# painel_meb.net
KiCad netlist of a schematic drawn in Altium Designer
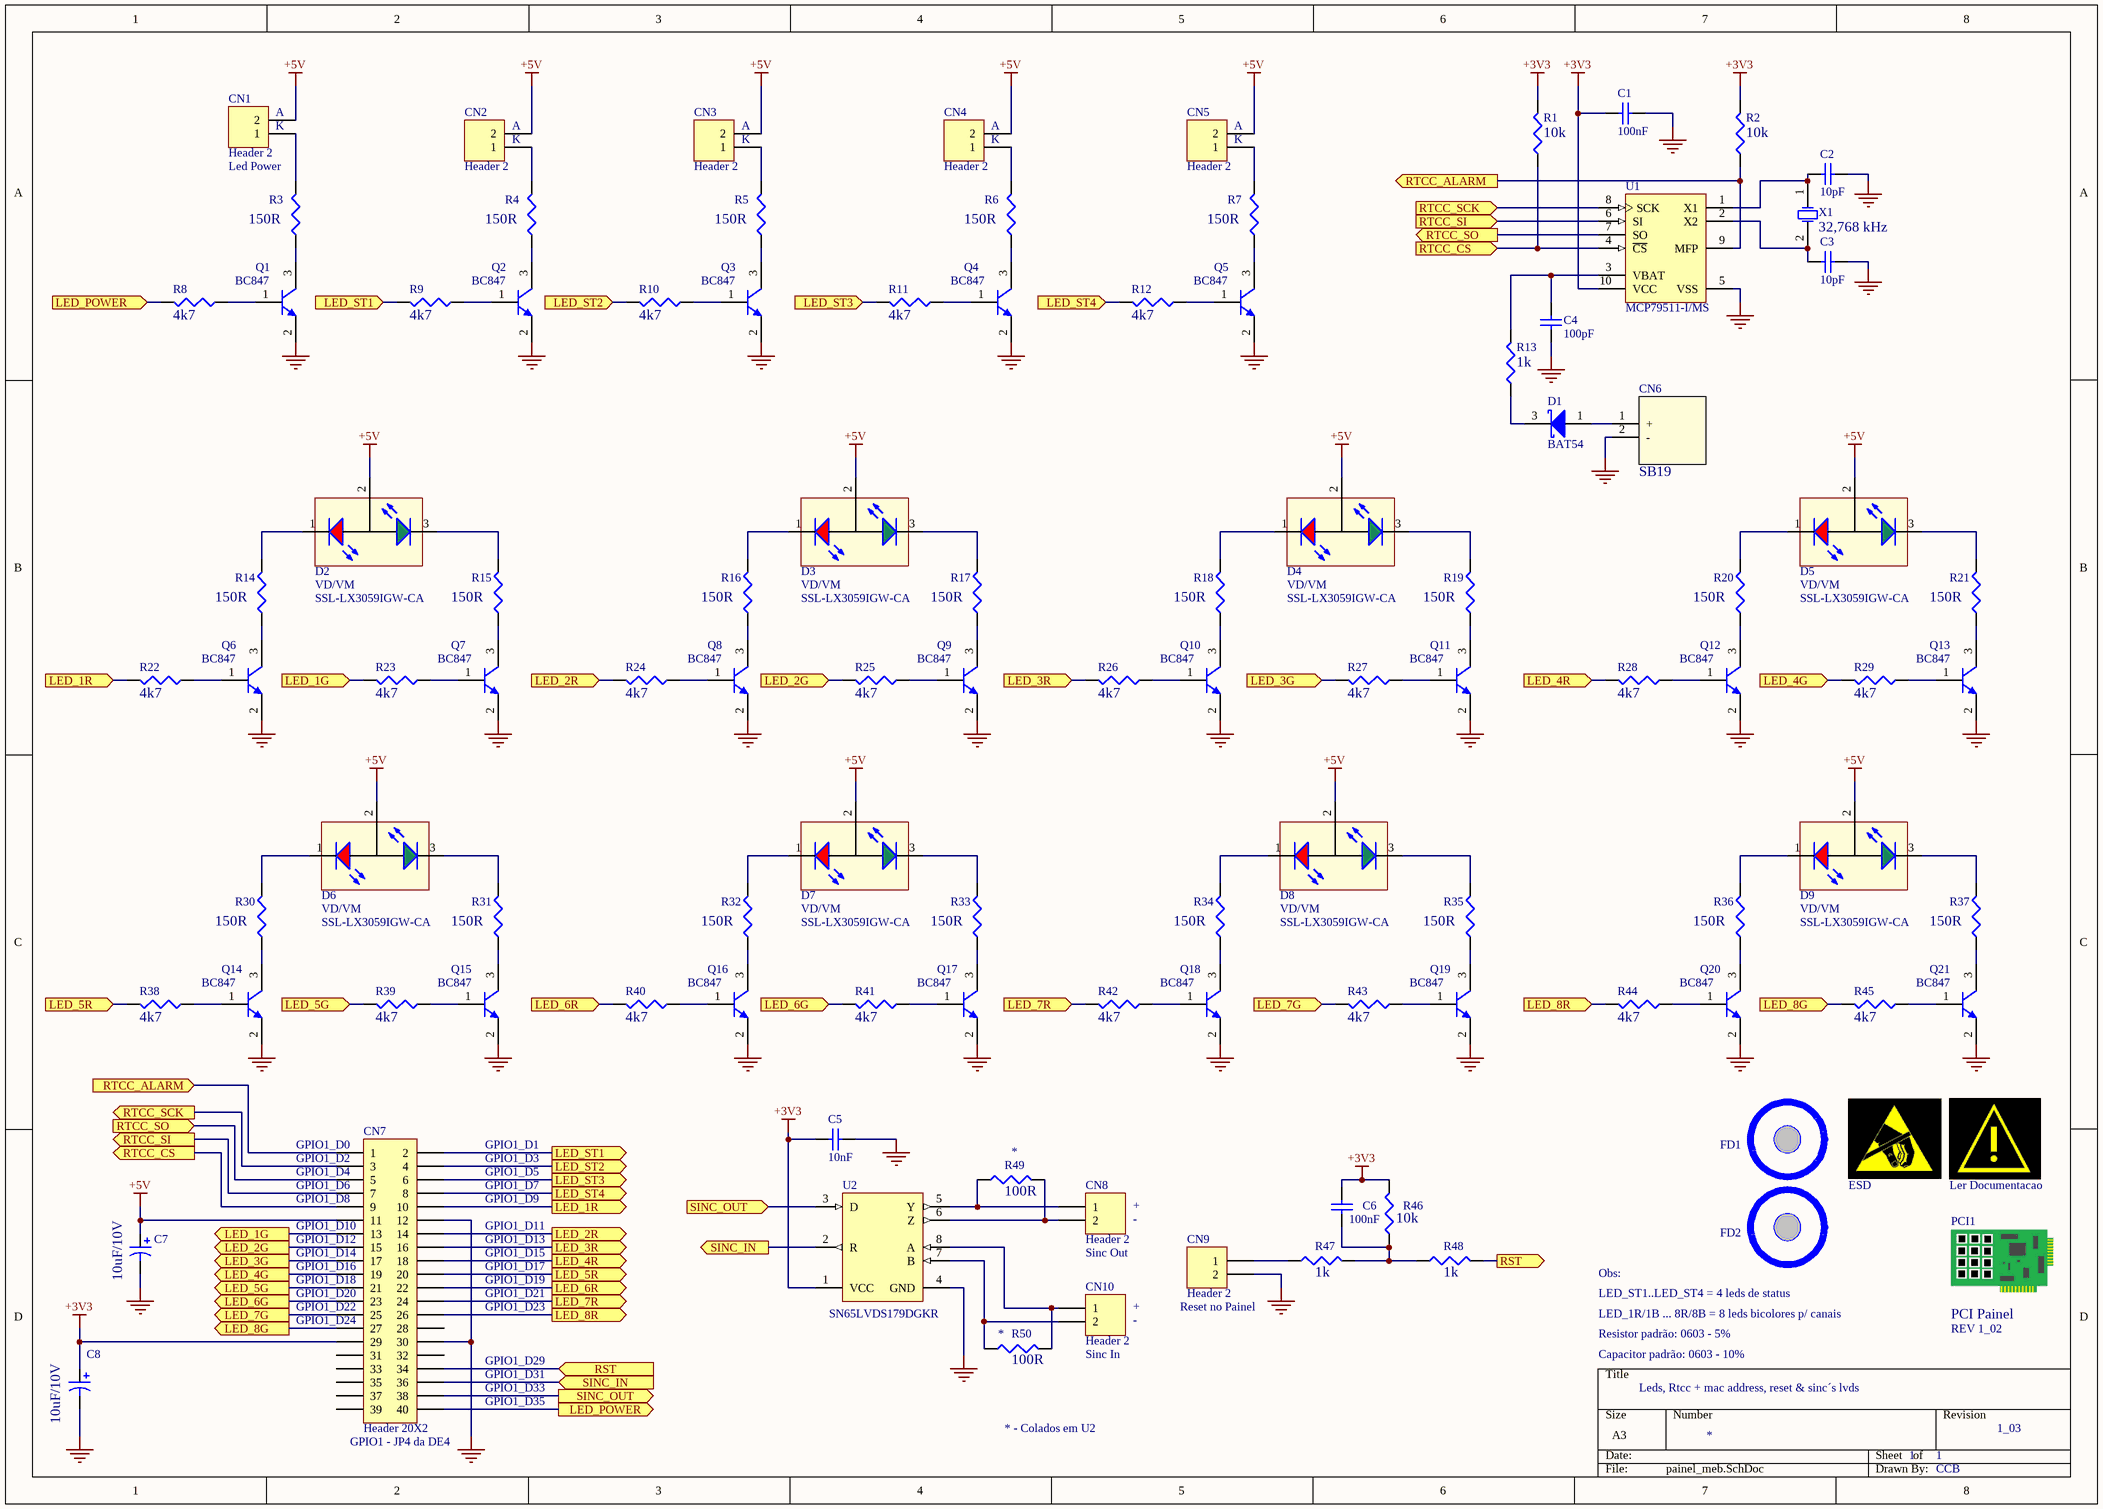
[diagram p0: painel_meb.SchDoc]

(export (version "E")
  (design (tool "Eeschema 10.0.6"))
  (components
    (comp (ref "AT1")
      (value "##nl")
      (footprint "LEIA_DOCUMENTACAO")
      (description "ATENCAO")
      (fields (field (name "VALOR") "Ler Documentacao"))
      (libsource (lib "SIMBOLOS") (part "ATENCAO"))
    )
    (comp (ref "C1")
      (value "Capacitor Cerâmico SMD")
      (footprint "0603 - CAP - montagem na maquina")
      (fields (field (name "VALOR") "100nF"))
      (libsource (lib "Miscellaneous Devices") (part "Capacitor Cerâmico SMD"))
    )
    (comp (ref "C2")
      (value "Capacitor Cerâmico SMD")
      (footprint "0603 - CAP - montagem na maquina")
      (fields (field (name "VALOR") "10pF"))
      (libsource (lib "Miscellaneous Devices") (part "Capacitor Cerâmico SMD"))
    )
    (comp (ref "C3")
      (value "Capacitor Cerâmico SMD")
      (footprint "0603 - CAP - montagem na maquina")
      (fields (field (name "VALOR") "10pF"))
      (libsource (lib "Miscellaneous Devices") (part "Capacitor Cerâmico SMD"))
    )
    (comp (ref "C4")
      (value "Capacitor Cerâmico SMD")
      (footprint "0603 - CAP - montagem na maquina")
      (fields (field (name "VALOR") "100pF"))
      (libsource (lib "Miscellaneous Devices") (part "Capacitor Cerâmico SMD"))
    )
    (comp (ref "C5")
      (value "Capacitor Cerâmico SMD")
      (footprint "0603 - CAP - montagem na maquina")
      (fields (field (name "VALOR") "10nF"))
      (libsource (lib "Miscellaneous Devices") (part "Capacitor Cerâmico SMD"))
    )
    (comp (ref "C6")
      (value "Capacitor Cerâmico SMD")
      (footprint "0603 - CAP - montagem na maquina")
      (fields (field (name "VALOR") "100nF"))
      (libsource (lib "Miscellaneous Devices") (part "Capacitor Cerâmico SMD"))
    )
    (comp (ref "C7")
      (value "Capacitor de tântalo")
      (footprint "CASE-B")
      (fields (field (name "VALOR") "10uF/10V"))
      (libsource (lib "Miscellaneous Devices") (part "Capacitor de tântalo"))
    )
    (comp (ref "C8")
      (value "Capacitor de tântalo")
      (footprint "CASE-B")
      (fields (field (name "VALOR") "10uF/10V"))
      (libsource (lib "Miscellaneous Devices") (part "Capacitor de tântalo"))
    )
    (comp (ref "CN1")
      (value "Header 2")
      (footprint "HDR1X2")
      (description "Header, 2-Pin")
      (fields (field (name "PUBLISHER") "Altium Limited"))
      (libsource (lib "Miscellaneous Connectors") (part "Header 2"))
    )
    (comp (ref "CN2")
      (value "Header 2")
      (footprint "HDR1X2")
      (description "Header, 2-Pin")
      (fields (field (name "PUBLISHER") "Altium Limited"))
      (libsource (lib "Miscellaneous Connectors") (part "Header 2"))
    )
    (comp (ref "CN3")
      (value "Header 2")
      (footprint "HDR1X2")
      (description "Header, 2-Pin")
      (fields (field (name "PUBLISHER") "Altium Limited"))
      (libsource (lib "Miscellaneous Connectors") (part "Header 2"))
    )
    (comp (ref "CN4")
      (value "Header 2")
      (footprint "HDR1X2")
      (description "Header, 2-Pin")
      (fields (field (name "PUBLISHER") "Altium Limited"))
      (libsource (lib "Miscellaneous Connectors") (part "Header 2"))
    )
    (comp (ref "CN5")
      (value "Header 2")
      (footprint "HDR1X2")
      (description "Header, 2-Pin")
      (fields (field (name "PUBLISHER") "Altium Limited"))
      (libsource (lib "Miscellaneous Connectors") (part "Header 2"))
    )
    (comp (ref "CN6")
      (value "11.0137")
      (footprint "Soquete para bateria SB19")
      (description "Soquete para Bateria CR2032")
      (fields (field (name "PART NUMBER") "SB19"))
      (libsource (lib "METALTEX") (part "Soquete para Bateria CR2032"))
    )
    (comp (ref "CN7")
      (value "Header 20X2")
      (footprint "HDR2X20")
      (description "Header, 20-Pin, Dual row")
      (fields (field (name "PUBLISHER") "Altium Limited"))
      (libsource (lib "Miscellaneous Connectors") (part "Header 20X2"))
    )
    (comp (ref "CN8")
      (value "Header 2")
      (footprint "HDR1X2")
      (description "Header, 2-Pin")
      (fields (field (name "PUBLISHER") "Altium Limited"))
      (libsource (lib "") (part "Header 2_1"))
    )
    (comp (ref "CN9")
      (value "Header 2")
      (footprint "HDR1X2")
      (description "Header, 2-Pin")
      (fields (field (name "PUBLISHER") "Altium Limited"))
      (libsource (lib "") (part "Header 2_2"))
    )
    (comp (ref "CN10")
      (value "Header 2")
      (footprint "HDR1X2")
      (description "Header, 2-Pin")
      (fields (field (name "PUBLISHER") "Altium Limited"))
      (libsource (lib "") (part "Header 2_1"))
    )
    (comp (ref "D1")
      (value "04.0100")
      (footprint "SOT23-3N - BAT54FAIRCHILD")
      (description "Diodo Schottky")
      (fields (field (name "PART NUMBER") "BAT54"))
      (libsource (lib "FSC Discrete Diode") (part "BAT54"))
    )
    (comp (ref "D2")
      (value "SSL-LX3059IGW-CA")
      (footprint "Led 3mm bicolor")
      (description "Led bicolor pth 3mm verde/vermelho")
      (fields (field (name "VALOR") "VD/VM") (field (name "PART NUMBER") "SSL-LX3059IGW-CA"))
      (libsource (lib "lumex") (part "SSL-LX3059IGW-CA"))
    )
    (comp (ref "D3")
      (value "SSL-LX3059IGW-CA")
      (footprint "Led 3mm bicolor")
      (description "Led bicolor pth 3mm verde/vermelho")
      (fields (field (name "VALOR") "VD/VM") (field (name "PART NUMBER") "SSL-LX3059IGW-CA"))
      (libsource (lib "lumex") (part "SSL-LX3059IGW-CA"))
    )
    (comp (ref "D4")
      (value "SSL-LX3059IGW-CA")
      (footprint "Led 3mm bicolor")
      (description "Led bicolor pth 3mm verde/vermelho")
      (fields (field (name "VALOR") "VD/VM") (field (name "PART NUMBER") "SSL-LX3059IGW-CA"))
      (libsource (lib "lumex") (part "SSL-LX3059IGW-CA"))
    )
    (comp (ref "D5")
      (value "SSL-LX3059IGW-CA")
      (footprint "Led 3mm bicolor")
      (description "Led bicolor pth 3mm verde/vermelho")
      (fields (field (name "VALOR") "VD/VM") (field (name "PART NUMBER") "SSL-LX3059IGW-CA"))
      (libsource (lib "lumex") (part "SSL-LX3059IGW-CA"))
    )
    (comp (ref "D6")
      (value "SSL-LX3059IGW-CA")
      (footprint "Led 3mm bicolor")
      (description "Led bicolor pth 3mm verde/vermelho")
      (fields (field (name "VALOR") "VD/VM") (field (name "PART NUMBER") "SSL-LX3059IGW-CA"))
      (libsource (lib "lumex") (part "SSL-LX3059IGW-CA"))
    )
    (comp (ref "D7")
      (value "SSL-LX3059IGW-CA")
      (footprint "Led 3mm bicolor")
      (description "Led bicolor pth 3mm verde/vermelho")
      (fields (field (name "VALOR") "VD/VM") (field (name "PART NUMBER") "SSL-LX3059IGW-CA"))
      (libsource (lib "lumex") (part "SSL-LX3059IGW-CA"))
    )
    (comp (ref "D8")
      (value "SSL-LX3059IGW-CA")
      (footprint "Led 3mm bicolor")
      (description "Led bicolor pth 3mm verde/vermelho")
      (fields (field (name "VALOR") "VD/VM") (field (name "PART NUMBER") "SSL-LX3059IGW-CA"))
      (libsource (lib "lumex") (part "SSL-LX3059IGW-CA"))
    )
    (comp (ref "D9")
      (value "SSL-LX3059IGW-CA")
      (footprint "Led 3mm bicolor")
      (description "Led bicolor pth 3mm verde/vermelho")
      (fields (field (name "VALOR") "VD/VM") (field (name "PART NUMBER") "SSL-LX3059IGW-CA"))
      (libsource (lib "lumex") (part "SSL-LX3059IGW-CA"))
    )
    (comp (ref "ESD1")
      (value "##nl")
      (footprint "ESTATICA")
      (description "ESD")
      (fields (field (name "VALOR") "ESD"))
      (libsource (lib "SIMBOLOS") (part "ESD"))
    )
    (comp (ref "FD1")
      (value "##nl")
      (footprint "FIDUCIAL")
      (description "Fiducial")
      (libsource (lib "PERIFERICOS") (part "Fiducial"))
    )
    (comp (ref "FD2")
      (value "##nl")
      (footprint "FIDUCIAL")
      (description "Fiducial")
      (libsource (lib "PERIFERICOS") (part "Fiducial"))
    )
    (comp (ref "PCI1")
      (value "30.????")
      (description "PCI")
      (fields (field (name "VALOR") "PCI Painel") (field (name "REV") "REV 1_02"))
      (libsource (lib "PCI") (part "PCI"))
    )
    (comp (ref "Q1")
      (value "QNPN")
      (footprint "SOT-23B")
      (description "NPN Bipolar Transistor")
      (fields (field (name "ALTIUM_UNNAMED_1") "BC847") (field (name "PUBLISHER") "Altium Limited"))
      (libsource (lib "Miscellaneous Devices") (part "QNPN"))
    )
    (comp (ref "Q2")
      (value "QNPN")
      (footprint "SOT-23B")
      (description "NPN Bipolar Transistor")
      (fields (field (name "VALOR") "BC847") (field (name "PUBLISHER") "Altium Limited"))
      (libsource (lib "Miscellaneous Devices") (part "QNPN"))
    )
    (comp (ref "Q3")
      (value "QNPN")
      (footprint "SOT-23B")
      (description "NPN Bipolar Transistor")
      (fields (field (name "ALTIUM_UNNAMED_1") "BC847") (field (name "PUBLISHER") "Altium Limited"))
      (libsource (lib "Miscellaneous Devices") (part "QNPN"))
    )
    (comp (ref "Q4")
      (value "QNPN")
      (footprint "SOT-23B")
      (description "NPN Bipolar Transistor")
      (fields (field (name "ALTIUM_UNNAMED_1") "BC847") (field (name "PUBLISHER") "Altium Limited"))
      (libsource (lib "Miscellaneous Devices") (part "QNPN"))
    )
    (comp (ref "Q5")
      (value "QNPN")
      (footprint "SOT-23B")
      (description "NPN Bipolar Transistor")
      (fields (field (name "ALTIUM_UNNAMED_1") "BC847") (field (name "PUBLISHER") "Altium Limited"))
      (libsource (lib "Miscellaneous Devices") (part "QNPN"))
    )
    (comp (ref "Q6")
      (value "QNPN")
      (footprint "SOT-23B")
      (description "NPN Bipolar Transistor")
      (fields (field (name "ALTIUM_UNNAMED_1") "BC847") (field (name "PUBLISHER") "Altium Limited"))
      (libsource (lib "Miscellaneous Devices") (part "QNPN"))
    )
    (comp (ref "Q7")
      (value "QNPN")
      (footprint "SOT-23B")
      (description "NPN Bipolar Transistor")
      (fields (field (name "ALTIUM_UNNAMED_1") "BC847") (field (name "PUBLISHER") "Altium Limited"))
      (libsource (lib "Miscellaneous Devices") (part "QNPN"))
    )
    (comp (ref "Q8")
      (value "QNPN")
      (footprint "SOT-23B")
      (description "NPN Bipolar Transistor")
      (fields (field (name "ALTIUM_UNNAMED_1") "BC847") (field (name "PUBLISHER") "Altium Limited"))
      (libsource (lib "Miscellaneous Devices") (part "QNPN"))
    )
    (comp (ref "Q9")
      (value "QNPN")
      (footprint "SOT-23B")
      (description "NPN Bipolar Transistor")
      (fields (field (name "ALTIUM_UNNAMED_1") "BC847") (field (name "PUBLISHER") "Altium Limited"))
      (libsource (lib "Miscellaneous Devices") (part "QNPN"))
    )
    (comp (ref "Q10")
      (value "QNPN")
      (footprint "SOT-23B")
      (description "NPN Bipolar Transistor")
      (fields (field (name "ALTIUM_UNNAMED_1") "BC847") (field (name "PUBLISHER") "Altium Limited"))
      (libsource (lib "Miscellaneous Devices") (part "QNPN"))
    )
    (comp (ref "Q11")
      (value "QNPN")
      (footprint "SOT-23B")
      (description "NPN Bipolar Transistor")
      (fields (field (name "ALTIUM_UNNAMED_1") "BC847") (field (name "PUBLISHER") "Altium Limited"))
      (libsource (lib "Miscellaneous Devices") (part "QNPN"))
    )
    (comp (ref "Q12")
      (value "QNPN")
      (footprint "SOT-23B")
      (description "NPN Bipolar Transistor")
      (fields (field (name "ALTIUM_UNNAMED_1") "BC847") (field (name "PUBLISHER") "Altium Limited"))
      (libsource (lib "Miscellaneous Devices") (part "QNPN"))
    )
    (comp (ref "Q13")
      (value "QNPN")
      (footprint "SOT-23B")
      (description "NPN Bipolar Transistor")
      (fields (field (name "ALTIUM_UNNAMED_1") "BC847") (field (name "PUBLISHER") "Altium Limited"))
      (libsource (lib "Miscellaneous Devices") (part "QNPN"))
    )
    (comp (ref "Q14")
      (value "QNPN")
      (footprint "SOT-23B")
      (description "NPN Bipolar Transistor")
      (fields (field (name "ALTIUM_UNNAMED_1") "BC847") (field (name "PUBLISHER") "Altium Limited"))
      (libsource (lib "Miscellaneous Devices") (part "QNPN"))
    )
    (comp (ref "Q15")
      (value "QNPN")
      (footprint "SOT-23B")
      (description "NPN Bipolar Transistor")
      (fields (field (name "ALTIUM_UNNAMED_1") "BC847") (field (name "PUBLISHER") "Altium Limited"))
      (libsource (lib "Miscellaneous Devices") (part "QNPN"))
    )
    (comp (ref "Q16")
      (value "QNPN")
      (footprint "SOT-23B")
      (description "NPN Bipolar Transistor")
      (fields (field (name "ALTIUM_UNNAMED_1") "BC847") (field (name "PUBLISHER") "Altium Limited"))
      (libsource (lib "Miscellaneous Devices") (part "QNPN"))
    )
    (comp (ref "Q17")
      (value "QNPN")
      (footprint "SOT-23B")
      (description "NPN Bipolar Transistor")
      (fields (field (name "ALTIUM_UNNAMED_1") "BC847") (field (name "PUBLISHER") "Altium Limited"))
      (libsource (lib "Miscellaneous Devices") (part "QNPN"))
    )
    (comp (ref "Q18")
      (value "QNPN")
      (footprint "SOT-23B")
      (description "NPN Bipolar Transistor")
      (fields (field (name "ALTIUM_UNNAMED_1") "BC847") (field (name "PUBLISHER") "Altium Limited"))
      (libsource (lib "Miscellaneous Devices") (part "QNPN"))
    )
    (comp (ref "Q19")
      (value "QNPN")
      (footprint "SOT-23B")
      (description "NPN Bipolar Transistor")
      (fields (field (name "ALTIUM_UNNAMED_1") "BC847") (field (name "PUBLISHER") "Altium Limited"))
      (libsource (lib "Miscellaneous Devices") (part "QNPN"))
    )
    (comp (ref "Q20")
      (value "QNPN")
      (footprint "SOT-23B")
      (description "NPN Bipolar Transistor")
      (fields (field (name "ALTIUM_UNNAMED_1") "BC847") (field (name "PUBLISHER") "Altium Limited"))
      (libsource (lib "Miscellaneous Devices") (part "QNPN"))
    )
    (comp (ref "Q21")
      (value "QNPN")
      (footprint "SOT-23B")
      (description "NPN Bipolar Transistor")
      (fields (field (name "ALTIUM_UNNAMED_1") "BC847") (field (name "PUBLISHER") "Altium Limited"))
      (libsource (lib "Miscellaneous Devices") (part "QNPN"))
    )
    (comp (ref "R1")
      (value "Res3")
      (footprint "0603 - MONTAGEM MÁQUINA")
      (description "Resistor")
      (fields (field (name "VALOR") "10k"))
      (libsource (lib "Miscellaneous Devices") (part "Res3"))
    )
    (comp (ref "R2")
      (value "Res3")
      (footprint "0603 - MONTAGEM MÁQUINA")
      (description "Resistor")
      (fields (field (name "VALOR") "10k"))
      (libsource (lib "Miscellaneous Devices") (part "Res3"))
    )
    (comp (ref "R3")
      (value "Res3")
      (footprint "0603 - MONTAGEM MÁQUINA")
      (description "Resistor")
      (fields (field (name "VALOR") "150R"))
      (libsource (lib "Miscellaneous Devices") (part "Res3"))
    )
    (comp (ref "R4")
      (value "Res3")
      (footprint "0603 - MONTAGEM MÁQUINA")
      (description "Resistor")
      (fields (field (name "VALOR") "150R"))
      (libsource (lib "Miscellaneous Devices") (part "Res3"))
    )
    (comp (ref "R5")
      (value "Res3")
      (footprint "0603 - MONTAGEM MÁQUINA")
      (description "Resistor")
      (fields (field (name "VALOR") "150R"))
      (libsource (lib "Miscellaneous Devices") (part "Res3"))
    )
    (comp (ref "R6")
      (value "Res3")
      (footprint "0603 - MONTAGEM MÁQUINA")
      (description "Resistor")
      (fields (field (name "VALOR") "150R"))
      (libsource (lib "Miscellaneous Devices") (part "Res3"))
    )
    (comp (ref "R7")
      (value "Res3")
      (footprint "0603 - MONTAGEM MÁQUINA")
      (description "Resistor")
      (fields (field (name "VALOR") "150R"))
      (libsource (lib "Miscellaneous Devices") (part "Res3"))
    )
    (comp (ref "R8")
      (value "Res3")
      (footprint "0603 - MONTAGEM MÁQUINA")
      (description "Resistor")
      (fields (field (name "VALOR") "4k7"))
      (libsource (lib "Miscellaneous Devices") (part "Res3"))
    )
    (comp (ref "R9")
      (value "Res3")
      (footprint "0603 - MONTAGEM MÁQUINA")
      (description "Resistor")
      (fields (field (name "VALOR") "4k7"))
      (libsource (lib "Miscellaneous Devices") (part "Res3"))
    )
    (comp (ref "R10")
      (value "Res3")
      (footprint "0603 - MONTAGEM MÁQUINA")
      (description "Resistor")
      (fields (field (name "VALOR") "4k7"))
      (libsource (lib "Miscellaneous Devices") (part "Res3"))
    )
    (comp (ref "R11")
      (value "Res3")
      (footprint "0603 - MONTAGEM MÁQUINA")
      (description "Resistor")
      (fields (field (name "VALOR") "4k7"))
      (libsource (lib "Miscellaneous Devices") (part "Res3"))
    )
    (comp (ref "R12")
      (value "Res3")
      (footprint "0603 - MONTAGEM MÁQUINA")
      (description "Resistor")
      (fields (field (name "VALOR") "4k7"))
      (libsource (lib "Miscellaneous Devices") (part "Res3"))
    )
    (comp (ref "R13")
      (value "Res3")
      (footprint "0603 - MONTAGEM MÁQUINA")
      (description "Resistor")
      (fields (field (name "VALOR") "1k"))
      (libsource (lib "Miscellaneous Devices") (part "Res3"))
    )
    (comp (ref "R14")
      (value "Res3")
      (footprint "0603 - MONTAGEM MÁQUINA")
      (description "Resistor")
      (fields (field (name "VALOR") "150R"))
      (libsource (lib "Miscellaneous Devices") (part "Res3"))
    )
    (comp (ref "R15")
      (value "Res3")
      (footprint "0603 - MONTAGEM MÁQUINA")
      (description "Resistor")
      (fields (field (name "VALOR") "150R"))
      (libsource (lib "Miscellaneous Devices") (part "Res3"))
    )
    (comp (ref "R16")
      (value "Res3")
      (footprint "0603 - MONTAGEM MÁQUINA")
      (description "Resistor")
      (fields (field (name "VALOR") "150R"))
      (libsource (lib "Miscellaneous Devices") (part "Res3"))
    )
    (comp (ref "R17")
      (value "Res3")
      (footprint "0603 - MONTAGEM MÁQUINA")
      (description "Resistor")
      (fields (field (name "VALOR") "150R"))
      (libsource (lib "Miscellaneous Devices") (part "Res3"))
    )
    (comp (ref "R18")
      (value "Res3")
      (footprint "0603 - MONTAGEM MÁQUINA")
      (description "Resistor")
      (fields (field (name "VALOR") "150R"))
      (libsource (lib "Miscellaneous Devices") (part "Res3"))
    )
    (comp (ref "R19")
      (value "Res3")
      (footprint "0603 - MONTAGEM MÁQUINA")
      (description "Resistor")
      (fields (field (name "VALOR") "150R"))
      (libsource (lib "Miscellaneous Devices") (part "Res3"))
    )
    (comp (ref "R20")
      (value "Res3")
      (footprint "0603 - MONTAGEM MÁQUINA")
      (description "Resistor")
      (fields (field (name "VALOR") "150R"))
      (libsource (lib "Miscellaneous Devices") (part "Res3"))
    )
    (comp (ref "R21")
      (value "Res3")
      (footprint "0603 - MONTAGEM MÁQUINA")
      (description "Resistor")
      (fields (field (name "VALOR") "150R"))
      (libsource (lib "Miscellaneous Devices") (part "Res3"))
    )
    (comp (ref "R22")
      (value "Res3")
      (footprint "0603 - MONTAGEM MÁQUINA")
      (description "Resistor")
      (fields (field (name "VALOR") "4k7"))
      (libsource (lib "Miscellaneous Devices") (part "Res3"))
    )
    (comp (ref "R23")
      (value "Res3")
      (footprint "0603 - MONTAGEM MÁQUINA")
      (description "Resistor")
      (fields (field (name "VALOR") "4k7"))
      (libsource (lib "Miscellaneous Devices") (part "Res3"))
    )
    (comp (ref "R24")
      (value "Res3")
      (footprint "0603 - MONTAGEM MÁQUINA")
      (description "Resistor")
      (fields (field (name "VALOR") "4k7"))
      (libsource (lib "Miscellaneous Devices") (part "Res3"))
    )
    (comp (ref "R25")
      (value "Res3")
      (footprint "0603 - MONTAGEM MÁQUINA")
      (description "Resistor")
      (fields (field (name "VALOR") "4k7"))
      (libsource (lib "Miscellaneous Devices") (part "Res3"))
    )
    (comp (ref "R26")
      (value "Res3")
      (footprint "0603 - MONTAGEM MÁQUINA")
      (description "Resistor")
      (fields (field (name "VALOR") "4k7"))
      (libsource (lib "Miscellaneous Devices") (part "Res3"))
    )
    (comp (ref "R27")
      (value "Res3")
      (footprint "0603 - MONTAGEM MÁQUINA")
      (description "Resistor")
      (fields (field (name "VALOR") "4k7"))
      (libsource (lib "Miscellaneous Devices") (part "Res3"))
    )
    (comp (ref "R28")
      (value "Res3")
      (footprint "0603 - MONTAGEM MÁQUINA")
      (description "Resistor")
      (fields (field (name "VALOR") "4k7"))
      (libsource (lib "Miscellaneous Devices") (part "Res3"))
    )
    (comp (ref "R29")
      (value "Res3")
      (footprint "0603 - MONTAGEM MÁQUINA")
      (description "Resistor")
      (fields (field (name "VALOR") "4k7"))
      (libsource (lib "Miscellaneous Devices") (part "Res3"))
    )
    (comp (ref "R30")
      (value "Res3")
      (footprint "0603 - MONTAGEM MÁQUINA")
      (description "Resistor")
      (fields (field (name "VALOR") "150R"))
      (libsource (lib "Miscellaneous Devices") (part "Res3"))
    )
    (comp (ref "R31")
      (value "Res3")
      (footprint "0603 - MONTAGEM MÁQUINA")
      (description "Resistor")
      (fields (field (name "VALOR") "150R"))
      (libsource (lib "Miscellaneous Devices") (part "Res3"))
    )
    (comp (ref "R32")
      (value "Res3")
      (footprint "0603 - MONTAGEM MÁQUINA")
      (description "Resistor")
      (fields (field (name "VALOR") "150R"))
      (libsource (lib "Miscellaneous Devices") (part "Res3"))
    )
    (comp (ref "R33")
      (value "Res3")
      (footprint "0603 - MONTAGEM MÁQUINA")
      (description "Resistor")
      (fields (field (name "VALOR") "150R"))
      (libsource (lib "Miscellaneous Devices") (part "Res3"))
    )
    (comp (ref "R34")
      (value "Res3")
      (footprint "0603 - MONTAGEM MÁQUINA")
      (description "Resistor")
      (fields (field (name "VALOR") "150R"))
      (libsource (lib "Miscellaneous Devices") (part "Res3"))
    )
    (comp (ref "R35")
      (value "Res3")
      (footprint "0603 - MONTAGEM MÁQUINA")
      (description "Resistor")
      (fields (field (name "VALOR") "150R"))
      (libsource (lib "Miscellaneous Devices") (part "Res3"))
    )
    (comp (ref "R36")
      (value "Res3")
      (footprint "0603 - MONTAGEM MÁQUINA")
      (description "Resistor")
      (fields (field (name "VALOR") "150R"))
      (libsource (lib "Miscellaneous Devices") (part "Res3"))
    )
    (comp (ref "R37")
      (value "Res3")
      (footprint "0603 - MONTAGEM MÁQUINA")
      (description "Resistor")
      (fields (field (name "VALOR") "150R"))
      (libsource (lib "Miscellaneous Devices") (part "Res3"))
    )
    (comp (ref "R38")
      (value "Res3")
      (footprint "0603 - MONTAGEM MÁQUINA")
      (description "Resistor")
      (fields (field (name "VALOR") "4k7"))
      (libsource (lib "Miscellaneous Devices") (part "Res3"))
    )
    (comp (ref "R39")
      (value "Res3")
      (footprint "0603 - MONTAGEM MÁQUINA")
      (description "Resistor")
      (fields (field (name "VALOR") "4k7"))
      (libsource (lib "Miscellaneous Devices") (part "Res3"))
    )
    (comp (ref "R40")
      (value "Res3")
      (footprint "0603 - MONTAGEM MÁQUINA")
      (description "Resistor")
      (fields (field (name "VALOR") "4k7"))
      (libsource (lib "Miscellaneous Devices") (part "Res3"))
    )
    (comp (ref "R41")
      (value "Res3")
      (footprint "0603 - MONTAGEM MÁQUINA")
      (description "Resistor")
      (fields (field (name "VALOR") "4k7"))
      (libsource (lib "Miscellaneous Devices") (part "Res3"))
    )
    (comp (ref "R42")
      (value "Res3")
      (footprint "0603 - MONTAGEM MÁQUINA")
      (description "Resistor")
      (fields (field (name "VALOR") "4k7"))
      (libsource (lib "Miscellaneous Devices") (part "Res3"))
    )
    (comp (ref "R43")
      (value "Res3")
      (footprint "0603 - MONTAGEM MÁQUINA")
      (description "Resistor")
      (fields (field (name "VALOR") "4k7"))
      (libsource (lib "Miscellaneous Devices") (part "Res3"))
    )
    (comp (ref "R44")
      (value "Res3")
      (footprint "0603 - MONTAGEM MÁQUINA")
      (description "Resistor")
      (fields (field (name "VALOR") "4k7"))
      (libsource (lib "Miscellaneous Devices") (part "Res3"))
    )
    (comp (ref "R45")
      (value "Res3")
      (footprint "0603 - MONTAGEM MÁQUINA")
      (description "Resistor")
      (fields (field (name "VALOR") "4k7"))
      (libsource (lib "Miscellaneous Devices") (part "Res3"))
    )
    (comp (ref "R46")
      (value "Res3")
      (footprint "0603 - MONTAGEM MÁQUINA")
      (description "Resistor")
      (fields (field (name "VALOR") "10k"))
      (libsource (lib "Miscellaneous Devices") (part "Res3"))
    )
    (comp (ref "R47")
      (value "Res3")
      (footprint "0603 - MONTAGEM MÁQUINA")
      (description "Resistor")
      (fields (field (name "VALOR") "1k"))
      (libsource (lib "Miscellaneous Devices") (part "Res3"))
    )
    (comp (ref "R48")
      (value "Res3")
      (footprint "0603 - MONTAGEM MÁQUINA")
      (description "Resistor")
      (fields (field (name "VALOR") "1k"))
      (libsource (lib "Miscellaneous Devices") (part "Res3"))
    )
    (comp (ref "R49")
      (value "Res3")
      (footprint "0603 - MONTAGEM MÁQUINA")
      (description "Resistor")
      (fields (field (name "VALOR") "100R"))
      (libsource (lib "Miscellaneous Devices") (part "Res3"))
    )
    (comp (ref "R50")
      (value "Res3")
      (footprint "0603 - MONTAGEM MÁQUINA")
      (description "Resistor")
      (fields (field (name "VALOR") "100R"))
      (libsource (lib "Miscellaneous Devices") (part "Res3"))
    )
    (comp (ref "U1")
      (value "MCP79511-I/MS")
      (footprint "MCHP-MSOP-MS10_N")
      (fields (field (name "MANUFACTURER") "Microchip"))
      (libsource (lib "Microchip Interface") (part "MCP79511-I/MS"))
    )
    (comp (ref "U2")
      (value "SN65LVDS179MDGKREP")
      (footprint "DGK8_L")
      (fields (field (name "MANUFACTURER") "Texas Instruments") (field (name "PARTNUMBER") "SN65LVDS179DGKR"))
      (libsource (lib "TI Interface LVDS M-LVDS ECL CML") (part "SN65LVDS179MDGKREP"))
    )
    (comp (ref "X1")
      (value "XTAL")
      (footprint "CRISTAL DT-38")
      (description "Cristal oscilador")
      (fields (field (name "VALOR") "32,768 kHz") (field (name "PUBLISHER") "Altium Limited"))
      (libsource (lib "Miscellaneous Devices") (part "XTAL"))
    )
  )
  (nets
    (net (code "1") (name "+3V3") (class "Default")
      (node (ref "C1") (pin "1") (pinfunction "1_1") (pintype "passive"))
      (node (ref "C5") (pin "1") (pinfunction "1_1") (pintype "passive"))
      (node (ref "C6") (pin "2") (pinfunction "2_2") (pintype "passive"))
      (node (ref "C8") (pin "1") (pinfunction "1_1") (pintype "passive"))
      (node (ref "CN7") (pin "29") (pinfunction "29_29") (pintype "passive"))
      (node (ref "R1") (pin "2") (pinfunction "2_2") (pintype "passive"))
      (node (ref "R2") (pin "2") (pinfunction "2_2") (pintype "passive"))
      (node (ref "R46") (pin "2") (pinfunction "2_2") (pintype "passive"))
      (node (ref "U1") (pin "10") (pinfunction "VCC_10") (pintype "power_in"))
      (node (ref "U2") (pin "1") (pinfunction "VCC_1") (pintype "power_in"))
    )
    (net (code "2") (name "+5V") (class "Default")
      (node (ref "C7") (pin "1") (pinfunction "1_1") (pintype "passive"))
      (node (ref "CN1") (pin "2") (pinfunction "2_2") (pintype "passive"))
      (node (ref "CN2") (pin "2") (pinfunction "2_2") (pintype "passive"))
      (node (ref "CN3") (pin "2") (pinfunction "2_2") (pintype "passive"))
      (node (ref "CN4") (pin "2") (pinfunction "2_2") (pintype "passive"))
      (node (ref "CN5") (pin "2") (pinfunction "2_2") (pintype "passive"))
      (node (ref "CN7") (pin "11") (pinfunction "11_11") (pintype "passive"))
      (node (ref "D2") (pin "2") (pinfunction "A_2") (pintype "passive"))
      (node (ref "D3") (pin "2") (pinfunction "A_2") (pintype "passive"))
      (node (ref "D4") (pin "2") (pinfunction "A_2") (pintype "passive"))
      (node (ref "D5") (pin "2") (pinfunction "A_2") (pintype "passive"))
      (node (ref "D6") (pin "2") (pinfunction "A_2") (pintype "passive"))
      (node (ref "D7") (pin "2") (pinfunction "A_2") (pintype "passive"))
      (node (ref "D8") (pin "2") (pinfunction "A_2") (pintype "passive"))
      (node (ref "D9") (pin "2") (pinfunction "A_2") (pintype "passive"))
    )
    (net (code "3") (name "/LED_1G") (class "Default")
      (node (ref "CN7") (pin "13") (pinfunction "13_13") (pintype "passive"))
      (node (ref "R23") (pin "2") (pinfunction "2_2") (pintype "passive"))
    )
    (net (code "4") (name "/LED_1R") (class "Default")
      (node (ref "CN7") (pin "10") (pinfunction "10_10") (pintype "passive"))
      (node (ref "R22") (pin "2") (pinfunction "2_2") (pintype "passive"))
    )
    (net (code "5") (name "/LED_2G") (class "Default")
      (node (ref "CN7") (pin "15") (pinfunction "15_15") (pintype "passive"))
      (node (ref "R25") (pin "2") (pinfunction "2_2") (pintype "passive"))
    )
    (net (code "6") (name "/LED_2R") (class "Default")
      (node (ref "CN7") (pin "14") (pinfunction "14_14") (pintype "passive"))
      (node (ref "R24") (pin "2") (pinfunction "2_2") (pintype "passive"))
    )
    (net (code "7") (name "/LED_3G") (class "Default")
      (node (ref "CN7") (pin "17") (pinfunction "17_17") (pintype "passive"))
      (node (ref "R27") (pin "2") (pinfunction "2_2") (pintype "passive"))
    )
    (net (code "8") (name "/LED_3R") (class "Default")
      (node (ref "CN7") (pin "16") (pinfunction "16_16") (pintype "passive"))
      (node (ref "R26") (pin "2") (pinfunction "2_2") (pintype "passive"))
    )
    (net (code "9") (name "/LED_4G") (class "Default")
      (node (ref "CN7") (pin "19") (pinfunction "19_19") (pintype "passive"))
      (node (ref "R29") (pin "2") (pinfunction "2_2") (pintype "passive"))
    )
    (net (code "10") (name "/LED_4R") (class "Default")
      (node (ref "CN7") (pin "18") (pinfunction "18_18") (pintype "passive"))
      (node (ref "R28") (pin "2") (pinfunction "2_2") (pintype "passive"))
    )
    (net (code "11") (name "/LED_5G") (class "Default")
      (node (ref "CN7") (pin "21") (pinfunction "21_21") (pintype "passive"))
      (node (ref "R39") (pin "2") (pinfunction "2_2") (pintype "passive"))
    )
    (net (code "12") (name "/LED_5R") (class "Default")
      (node (ref "CN7") (pin "20") (pinfunction "20_20") (pintype "passive"))
      (node (ref "R38") (pin "2") (pinfunction "2_2") (pintype "passive"))
    )
    (net (code "13") (name "/LED_6G") (class "Default")
      (node (ref "CN7") (pin "23") (pinfunction "23_23") (pintype "passive"))
      (node (ref "R41") (pin "2") (pinfunction "2_2") (pintype "passive"))
    )
    (net (code "14") (name "/LED_6R") (class "Default")
      (node (ref "CN7") (pin "22") (pinfunction "22_22") (pintype "passive"))
      (node (ref "R40") (pin "2") (pinfunction "2_2") (pintype "passive"))
    )
    (net (code "15") (name "/LED_7G") (class "Default")
      (node (ref "CN7") (pin "25") (pinfunction "25_25") (pintype "passive"))
      (node (ref "R43") (pin "2") (pinfunction "2_2") (pintype "passive"))
    )
    (net (code "16") (name "/LED_7R") (class "Default")
      (node (ref "CN7") (pin "24") (pinfunction "24_24") (pintype "passive"))
      (node (ref "R42") (pin "2") (pinfunction "2_2") (pintype "passive"))
    )
    (net (code "17") (name "/LED_8G") (class "Default")
      (node (ref "CN7") (pin "27") (pinfunction "27_27") (pintype "passive"))
      (node (ref "R45") (pin "2") (pinfunction "2_2") (pintype "passive"))
    )
    (net (code "18") (name "/LED_8R") (class "Default")
      (node (ref "CN7") (pin "26") (pinfunction "26_26") (pintype "passive"))
      (node (ref "R44") (pin "2") (pinfunction "2_2") (pintype "passive"))
    )
    (net (code "19") (name "/LED_POWER") (class "Default")
      (node (ref "CN7") (pin "40") (pinfunction "40_40") (pintype "passive"))
      (node (ref "R8") (pin "2") (pinfunction "2_2") (pintype "passive"))
    )
    (net (code "20") (name "/LED_ST1") (class "Default")
      (node (ref "CN7") (pin "2") (pinfunction "2_2") (pintype "passive"))
      (node (ref "R9") (pin "2") (pinfunction "2_2") (pintype "passive"))
    )
    (net (code "21") (name "/LED_ST2") (class "Default")
      (node (ref "CN7") (pin "4") (pinfunction "4_4") (pintype "passive"))
      (node (ref "R10") (pin "2") (pinfunction "2_2") (pintype "passive"))
    )
    (net (code "22") (name "/LED_ST3") (class "Default")
      (node (ref "CN7") (pin "6") (pinfunction "6_6") (pintype "passive"))
      (node (ref "R11") (pin "2") (pinfunction "2_2") (pintype "passive"))
    )
    (net (code "23") (name "/LED_ST4") (class "Default")
      (node (ref "CN7") (pin "8") (pinfunction "8_8") (pintype "passive"))
      (node (ref "R12") (pin "2") (pinfunction "2_2") (pintype "passive"))
    )
    (net (code "24") (name "/RST") (class "Default")
      (node (ref "CN7") (pin "34") (pinfunction "34_34") (pintype "passive"))
      (node (ref "R48") (pin "2") (pinfunction "2_2") (pintype "passive"))
    )
    (net (code "25") (name "/RTCC_ALARM") (class "Default")
      (node (ref "CN7") (pin "1") (pinfunction "1_1") (pintype "passive"))
      (node (ref "R2") (pin "1") (pinfunction "1_1") (pintype "passive"))
      (node (ref "U1") (pin "9") (pinfunction "MFP_9") (pintype "open_collector"))
    )
    (net (code "26") (name "/RTCC_CS") (class "Default")
      (node (ref "CN7") (pin "9") (pinfunction "9_9") (pintype "passive"))
      (node (ref "R1") (pin "1") (pinfunction "1_1") (pintype "passive"))
      (node (ref "U1") (pin "4") (pinfunction "~{CS}_4") (pintype "input"))
    )
    (net (code "27") (name "/RTCC_SCK") (class "Default")
      (node (ref "CN7") (pin "3") (pinfunction "3_3") (pintype "passive"))
      (node (ref "U1") (pin "8") (pinfunction "SCK_8") (pintype "input"))
    )
    (net (code "28") (name "/RTCC_SI") (class "Default")
      (node (ref "CN7") (pin "7") (pinfunction "7_7") (pintype "passive"))
      (node (ref "U1") (pin "6") (pinfunction "SI_6") (pintype "input"))
    )
    (net (code "29") (name "/RTCC_SO") (class "Default")
      (node (ref "CN7") (pin "5") (pinfunction "5_5") (pintype "passive"))
      (node (ref "U1") (pin "7") (pinfunction "SO_7") (pintype "tri_state"))
    )
    (net (code "30") (name "/SINC_IN") (class "Default")
      (node (ref "CN7") (pin "36") (pinfunction "36_36") (pintype "passive"))
      (node (ref "U2") (pin "2") (pinfunction "R_2") (pintype "output"))
    )
    (net (code "31") (name "/SINC_OUT") (class "Default")
      (node (ref "CN7") (pin "38") (pinfunction "38_38") (pintype "passive"))
      (node (ref "U2") (pin "3") (pinfunction "D_3") (pintype "input"))
    )
    (net (code "32") (name "GND") (class "Default")
      (node (ref "C1") (pin "2") (pinfunction "2_2") (pintype "passive"))
      (node (ref "C2") (pin "2") (pinfunction "2_2") (pintype "passive"))
      (node (ref "C3") (pin "2") (pinfunction "2_2") (pintype "passive"))
      (node (ref "C4") (pin "2") (pinfunction "2_2") (pintype "passive"))
      (node (ref "C5") (pin "2") (pinfunction "2_2") (pintype "passive"))
      (node (ref "C7") (pin "2") (pinfunction "2_2") (pintype "passive"))
      (node (ref "C8") (pin "2") (pinfunction "2_2") (pintype "passive"))
      (node (ref "CN6") (pin "2") (pinfunction "-_2") (pintype "passive"))
      (node (ref "CN7") (pin "12") (pinfunction "12_12") (pintype "passive"))
      (node (ref "CN7") (pin "30") (pinfunction "30_30") (pintype "passive"))
      (node (ref "CN9") (pin "2") (pinfunction "2_2") (pintype "passive"))
      (node (ref "Q1") (pin "2") (pinfunction "E_2") (pintype "passive"))
      (node (ref "Q10") (pin "2") (pinfunction "E_2") (pintype "passive"))
      (node (ref "Q11") (pin "2") (pinfunction "E_2") (pintype "passive"))
      (node (ref "Q12") (pin "2") (pinfunction "E_2") (pintype "passive"))
      (node (ref "Q13") (pin "2") (pinfunction "E_2") (pintype "passive"))
      (node (ref "Q14") (pin "2") (pinfunction "E_2") (pintype "passive"))
      (node (ref "Q15") (pin "2") (pinfunction "E_2") (pintype "passive"))
      (node (ref "Q16") (pin "2") (pinfunction "E_2") (pintype "passive"))
      (node (ref "Q17") (pin "2") (pinfunction "E_2") (pintype "passive"))
      (node (ref "Q18") (pin "2") (pinfunction "E_2") (pintype "passive"))
      (node (ref "Q19") (pin "2") (pinfunction "E_2") (pintype "passive"))
      (node (ref "Q2") (pin "2") (pinfunction "E_2") (pintype "passive"))
      (node (ref "Q20") (pin "2") (pinfunction "E_2") (pintype "passive"))
      (node (ref "Q21") (pin "2") (pinfunction "E_2") (pintype "passive"))
      (node (ref "Q3") (pin "2") (pinfunction "E_2") (pintype "passive"))
      (node (ref "Q4") (pin "2") (pinfunction "E_2") (pintype "passive"))
      (node (ref "Q5") (pin "2") (pinfunction "E_2") (pintype "passive"))
      (node (ref "Q6") (pin "2") (pinfunction "E_2") (pintype "passive"))
      (node (ref "Q7") (pin "2") (pinfunction "E_2") (pintype "passive"))
      (node (ref "Q8") (pin "2") (pinfunction "E_2") (pintype "passive"))
      (node (ref "Q9") (pin "2") (pinfunction "E_2") (pintype "passive"))
      (node (ref "U1") (pin "5") (pinfunction "VSS_5") (pintype "power_in"))
      (node (ref "U2") (pin "4") (pinfunction "GND_4") (pintype "power_in"))
    )
    (net (code "33") (name "Net-(C6-Pad1)") (class "Default")
      (node (ref "C6") (pin "1") (pinfunction "1_1") (pintype "passive"))
      (node (ref "R46") (pin "1") (pinfunction "1_1") (pintype "passive"))
      (node (ref "R47") (pin "2") (pinfunction "2_2") (pintype "passive"))
      (node (ref "R48") (pin "1") (pinfunction "1_1") (pintype "passive"))
    )
    (net (code "34") (name "Net-(CN1-Pad1)") (class "Default")
      (node (ref "CN1") (pin "1") (pinfunction "1_1") (pintype "passive"))
      (node (ref "R3") (pin "2") (pinfunction "2_2") (pintype "passive"))
    )
    (net (code "35") (name "Net-(CN2-Pad1)") (class "Default")
      (node (ref "CN2") (pin "1") (pinfunction "1_1") (pintype "passive"))
      (node (ref "R4") (pin "2") (pinfunction "2_2") (pintype "passive"))
    )
    (net (code "36") (name "Net-(CN3-Pad1)") (class "Default")
      (node (ref "CN3") (pin "1") (pinfunction "1_1") (pintype "passive"))
      (node (ref "R5") (pin "2") (pinfunction "2_2") (pintype "passive"))
    )
    (net (code "37") (name "Net-(CN4-Pad1)") (class "Default")
      (node (ref "CN4") (pin "1") (pinfunction "1_1") (pintype "passive"))
      (node (ref "R6") (pin "2") (pinfunction "2_2") (pintype "passive"))
    )
    (net (code "38") (name "Net-(CN5-Pad1)") (class "Default")
      (node (ref "CN5") (pin "1") (pinfunction "1_1") (pintype "passive"))
      (node (ref "R7") (pin "2") (pinfunction "2_2") (pintype "passive"))
    )
    (net (code "39") (name "Net-(CN6-+)") (class "Default")
      (node (ref "CN6") (pin "1") (pinfunction "+_1") (pintype "passive"))
      (node (ref "D1") (pin "1") (pinfunction "A_1") (pintype "passive"))
    )
    (net (code "40") (name "Net-(CN9-Pad1)") (class "Default")
      (node (ref "CN9") (pin "1") (pinfunction "1_1") (pintype "passive"))
      (node (ref "R47") (pin "1") (pinfunction "1_1") (pintype "passive"))
    )
    (net (code "41") (name "Net-(D1-K)") (class "Default")
      (node (ref "D1") (pin "3") (pinfunction "K_3") (pintype "passive"))
      (node (ref "R13") (pin "1") (pinfunction "1_1") (pintype "passive"))
    )
    (net (code "42") (name "Net-(D2-KG)") (class "Default")
      (node (ref "D2") (pin "3") (pinfunction "KG_3") (pintype "passive"))
      (node (ref "R15") (pin "2") (pinfunction "2_2") (pintype "passive"))
    )
    (net (code "43") (name "Net-(D2-KR)") (class "Default")
      (node (ref "D2") (pin "1") (pinfunction "KR_1") (pintype "passive"))
      (node (ref "R14") (pin "2") (pinfunction "2_2") (pintype "passive"))
    )
    (net (code "44") (name "Net-(D3-KG)") (class "Default")
      (node (ref "D3") (pin "3") (pinfunction "KG_3") (pintype "passive"))
      (node (ref "R17") (pin "2") (pinfunction "2_2") (pintype "passive"))
    )
    (net (code "45") (name "Net-(D3-KR)") (class "Default")
      (node (ref "D3") (pin "1") (pinfunction "KR_1") (pintype "passive"))
      (node (ref "R16") (pin "2") (pinfunction "2_2") (pintype "passive"))
    )
    (net (code "46") (name "Net-(D4-KG)") (class "Default")
      (node (ref "D4") (pin "3") (pinfunction "KG_3") (pintype "passive"))
      (node (ref "R19") (pin "2") (pinfunction "2_2") (pintype "passive"))
    )
    (net (code "47") (name "Net-(D4-KR)") (class "Default")
      (node (ref "D4") (pin "1") (pinfunction "KR_1") (pintype "passive"))
      (node (ref "R18") (pin "2") (pinfunction "2_2") (pintype "passive"))
    )
    (net (code "48") (name "Net-(D5-KG)") (class "Default")
      (node (ref "D5") (pin "3") (pinfunction "KG_3") (pintype "passive"))
      (node (ref "R21") (pin "2") (pinfunction "2_2") (pintype "passive"))
    )
    (net (code "49") (name "Net-(D5-KR)") (class "Default")
      (node (ref "D5") (pin "1") (pinfunction "KR_1") (pintype "passive"))
      (node (ref "R20") (pin "2") (pinfunction "2_2") (pintype "passive"))
    )
    (net (code "50") (name "Net-(D6-KG)") (class "Default")
      (node (ref "D6") (pin "3") (pinfunction "KG_3") (pintype "passive"))
      (node (ref "R31") (pin "2") (pinfunction "2_2") (pintype "passive"))
    )
    (net (code "51") (name "Net-(D6-KR)") (class "Default")
      (node (ref "D6") (pin "1") (pinfunction "KR_1") (pintype "passive"))
      (node (ref "R30") (pin "2") (pinfunction "2_2") (pintype "passive"))
    )
    (net (code "52") (name "Net-(D7-KG)") (class "Default")
      (node (ref "D7") (pin "3") (pinfunction "KG_3") (pintype "passive"))
      (node (ref "R33") (pin "2") (pinfunction "2_2") (pintype "passive"))
    )
    (net (code "53") (name "Net-(D7-KR)") (class "Default")
      (node (ref "D7") (pin "1") (pinfunction "KR_1") (pintype "passive"))
      (node (ref "R32") (pin "2") (pinfunction "2_2") (pintype "passive"))
    )
    (net (code "54") (name "Net-(D8-KG)") (class "Default")
      (node (ref "D8") (pin "3") (pinfunction "KG_3") (pintype "passive"))
      (node (ref "R35") (pin "2") (pinfunction "2_2") (pintype "passive"))
    )
    (net (code "55") (name "Net-(D8-KR)") (class "Default")
      (node (ref "D8") (pin "1") (pinfunction "KR_1") (pintype "passive"))
      (node (ref "R34") (pin "2") (pinfunction "2_2") (pintype "passive"))
    )
    (net (code "56") (name "Net-(D9-KG)") (class "Default")
      (node (ref "D9") (pin "3") (pinfunction "KG_3") (pintype "passive"))
      (node (ref "R37") (pin "2") (pinfunction "2_2") (pintype "passive"))
    )
    (net (code "57") (name "Net-(D9-KR)") (class "Default")
      (node (ref "D9") (pin "1") (pinfunction "KR_1") (pintype "passive"))
      (node (ref "R36") (pin "2") (pinfunction "2_2") (pintype "passive"))
    )
    (net (code "58") (name "Net-(Q1-B)") (class "Default")
      (node (ref "Q1") (pin "1") (pinfunction "B_1") (pintype "passive"))
      (node (ref "R8") (pin "1") (pinfunction "1_1") (pintype "passive"))
    )
    (net (code "59") (name "Net-(Q1-C)") (class "Default")
      (node (ref "Q1") (pin "3") (pinfunction "C_3") (pintype "passive"))
      (node (ref "R3") (pin "1") (pinfunction "1_1") (pintype "passive"))
    )
    (net (code "60") (name "Net-(Q2-B)") (class "Default")
      (node (ref "Q2") (pin "1") (pinfunction "B_1") (pintype "passive"))
      (node (ref "R9") (pin "1") (pinfunction "1_1") (pintype "passive"))
    )
    (net (code "61") (name "Net-(Q2-C)") (class "Default")
      (node (ref "Q2") (pin "3") (pinfunction "C_3") (pintype "passive"))
      (node (ref "R4") (pin "1") (pinfunction "1_1") (pintype "passive"))
    )
    (net (code "62") (name "Net-(Q3-B)") (class "Default")
      (node (ref "Q3") (pin "1") (pinfunction "B_1") (pintype "passive"))
      (node (ref "R10") (pin "1") (pinfunction "1_1") (pintype "passive"))
    )
    (net (code "63") (name "Net-(Q3-C)") (class "Default")
      (node (ref "Q3") (pin "3") (pinfunction "C_3") (pintype "passive"))
      (node (ref "R5") (pin "1") (pinfunction "1_1") (pintype "passive"))
    )
    (net (code "64") (name "Net-(Q4-B)") (class "Default")
      (node (ref "Q4") (pin "1") (pinfunction "B_1") (pintype "passive"))
      (node (ref "R11") (pin "1") (pinfunction "1_1") (pintype "passive"))
    )
    (net (code "65") (name "Net-(Q4-C)") (class "Default")
      (node (ref "Q4") (pin "3") (pinfunction "C_3") (pintype "passive"))
      (node (ref "R6") (pin "1") (pinfunction "1_1") (pintype "passive"))
    )
    (net (code "66") (name "Net-(Q5-B)") (class "Default")
      (node (ref "Q5") (pin "1") (pinfunction "B_1") (pintype "passive"))
      (node (ref "R12") (pin "1") (pinfunction "1_1") (pintype "passive"))
    )
    (net (code "67") (name "Net-(Q5-C)") (class "Default")
      (node (ref "Q5") (pin "3") (pinfunction "C_3") (pintype "passive"))
      (node (ref "R7") (pin "1") (pinfunction "1_1") (pintype "passive"))
    )
    (net (code "68") (name "Net-(Q6-B)") (class "Default")
      (node (ref "Q6") (pin "1") (pinfunction "B_1") (pintype "passive"))
      (node (ref "R22") (pin "1") (pinfunction "1_1") (pintype "passive"))
    )
    (net (code "69") (name "Net-(Q6-C)") (class "Default")
      (node (ref "Q6") (pin "3") (pinfunction "C_3") (pintype "passive"))
      (node (ref "R14") (pin "1") (pinfunction "1_1") (pintype "passive"))
    )
    (net (code "70") (name "Net-(Q7-B)") (class "Default")
      (node (ref "Q7") (pin "1") (pinfunction "B_1") (pintype "passive"))
      (node (ref "R23") (pin "1") (pinfunction "1_1") (pintype "passive"))
    )
    (net (code "71") (name "Net-(Q7-C)") (class "Default")
      (node (ref "Q7") (pin "3") (pinfunction "C_3") (pintype "passive"))
      (node (ref "R15") (pin "1") (pinfunction "1_1") (pintype "passive"))
    )
    (net (code "72") (name "Net-(Q8-B)") (class "Default")
      (node (ref "Q8") (pin "1") (pinfunction "B_1") (pintype "passive"))
      (node (ref "R24") (pin "1") (pinfunction "1_1") (pintype "passive"))
    )
    (net (code "73") (name "Net-(Q8-C)") (class "Default")
      (node (ref "Q8") (pin "3") (pinfunction "C_3") (pintype "passive"))
      (node (ref "R16") (pin "1") (pinfunction "1_1") (pintype "passive"))
    )
    (net (code "74") (name "Net-(Q9-B)") (class "Default")
      (node (ref "Q9") (pin "1") (pinfunction "B_1") (pintype "passive"))
      (node (ref "R25") (pin "1") (pinfunction "1_1") (pintype "passive"))
    )
    (net (code "75") (name "Net-(Q9-C)") (class "Default")
      (node (ref "Q9") (pin "3") (pinfunction "C_3") (pintype "passive"))
      (node (ref "R17") (pin "1") (pinfunction "1_1") (pintype "passive"))
    )
    (net (code "76") (name "Net-(Q10-B)") (class "Default")
      (node (ref "Q10") (pin "1") (pinfunction "B_1") (pintype "passive"))
      (node (ref "R26") (pin "1") (pinfunction "1_1") (pintype "passive"))
    )
    (net (code "77") (name "Net-(Q10-C)") (class "Default")
      (node (ref "Q10") (pin "3") (pinfunction "C_3") (pintype "passive"))
      (node (ref "R18") (pin "1") (pinfunction "1_1") (pintype "passive"))
    )
    (net (code "78") (name "Net-(Q11-B)") (class "Default")
      (node (ref "Q11") (pin "1") (pinfunction "B_1") (pintype "passive"))
      (node (ref "R27") (pin "1") (pinfunction "1_1") (pintype "passive"))
    )
    (net (code "79") (name "Net-(Q11-C)") (class "Default")
      (node (ref "Q11") (pin "3") (pinfunction "C_3") (pintype "passive"))
      (node (ref "R19") (pin "1") (pinfunction "1_1") (pintype "passive"))
    )
    (net (code "80") (name "Net-(Q12-B)") (class "Default")
      (node (ref "Q12") (pin "1") (pinfunction "B_1") (pintype "passive"))
      (node (ref "R28") (pin "1") (pinfunction "1_1") (pintype "passive"))
    )
    (net (code "81") (name "Net-(Q12-C)") (class "Default")
      (node (ref "Q12") (pin "3") (pinfunction "C_3") (pintype "passive"))
      (node (ref "R20") (pin "1") (pinfunction "1_1") (pintype "passive"))
    )
    (net (code "82") (name "Net-(Q13-B)") (class "Default")
      (node (ref "Q13") (pin "1") (pinfunction "B_1") (pintype "passive"))
      (node (ref "R29") (pin "1") (pinfunction "1_1") (pintype "passive"))
    )
    (net (code "83") (name "Net-(Q13-C)") (class "Default")
      (node (ref "Q13") (pin "3") (pinfunction "C_3") (pintype "passive"))
      (node (ref "R21") (pin "1") (pinfunction "1_1") (pintype "passive"))
    )
    (net (code "84") (name "Net-(Q14-B)") (class "Default")
      (node (ref "Q14") (pin "1") (pinfunction "B_1") (pintype "passive"))
      (node (ref "R38") (pin "1") (pinfunction "1_1") (pintype "passive"))
    )
    (net (code "85") (name "Net-(Q14-C)") (class "Default")
      (node (ref "Q14") (pin "3") (pinfunction "C_3") (pintype "passive"))
      (node (ref "R30") (pin "1") (pinfunction "1_1") (pintype "passive"))
    )
    (net (code "86") (name "Net-(Q15-B)") (class "Default")
      (node (ref "Q15") (pin "1") (pinfunction "B_1") (pintype "passive"))
      (node (ref "R39") (pin "1") (pinfunction "1_1") (pintype "passive"))
    )
    (net (code "87") (name "Net-(Q15-C)") (class "Default")
      (node (ref "Q15") (pin "3") (pinfunction "C_3") (pintype "passive"))
      (node (ref "R31") (pin "1") (pinfunction "1_1") (pintype "passive"))
    )
    (net (code "88") (name "Net-(Q16-B)") (class "Default")
      (node (ref "Q16") (pin "1") (pinfunction "B_1") (pintype "passive"))
      (node (ref "R40") (pin "1") (pinfunction "1_1") (pintype "passive"))
    )
    (net (code "89") (name "Net-(Q16-C)") (class "Default")
      (node (ref "Q16") (pin "3") (pinfunction "C_3") (pintype "passive"))
      (node (ref "R32") (pin "1") (pinfunction "1_1") (pintype "passive"))
    )
    (net (code "90") (name "Net-(Q17-B)") (class "Default")
      (node (ref "Q17") (pin "1") (pinfunction "B_1") (pintype "passive"))
      (node (ref "R41") (pin "1") (pinfunction "1_1") (pintype "passive"))
    )
    (net (code "91") (name "Net-(Q17-C)") (class "Default")
      (node (ref "Q17") (pin "3") (pinfunction "C_3") (pintype "passive"))
      (node (ref "R33") (pin "1") (pinfunction "1_1") (pintype "passive"))
    )
    (net (code "92") (name "Net-(Q18-B)") (class "Default")
      (node (ref "Q18") (pin "1") (pinfunction "B_1") (pintype "passive"))
      (node (ref "R42") (pin "1") (pinfunction "1_1") (pintype "passive"))
    )
    (net (code "93") (name "Net-(Q18-C)") (class "Default")
      (node (ref "Q18") (pin "3") (pinfunction "C_3") (pintype "passive"))
      (node (ref "R34") (pin "1") (pinfunction "1_1") (pintype "passive"))
    )
    (net (code "94") (name "Net-(Q19-B)") (class "Default")
      (node (ref "Q19") (pin "1") (pinfunction "B_1") (pintype "passive"))
      (node (ref "R43") (pin "1") (pinfunction "1_1") (pintype "passive"))
    )
    (net (code "95") (name "Net-(Q19-C)") (class "Default")
      (node (ref "Q19") (pin "3") (pinfunction "C_3") (pintype "passive"))
      (node (ref "R35") (pin "1") (pinfunction "1_1") (pintype "passive"))
    )
    (net (code "96") (name "Net-(Q20-B)") (class "Default")
      (node (ref "Q20") (pin "1") (pinfunction "B_1") (pintype "passive"))
      (node (ref "R44") (pin "1") (pinfunction "1_1") (pintype "passive"))
    )
    (net (code "97") (name "Net-(Q20-C)") (class "Default")
      (node (ref "Q20") (pin "3") (pinfunction "C_3") (pintype "passive"))
      (node (ref "R36") (pin "1") (pinfunction "1_1") (pintype "passive"))
    )
    (net (code "98") (name "Net-(Q21-B)") (class "Default")
      (node (ref "Q21") (pin "1") (pinfunction "B_1") (pintype "passive"))
      (node (ref "R45") (pin "1") (pinfunction "1_1") (pintype "passive"))
    )
    (net (code "99") (name "Net-(Q21-C)") (class "Default")
      (node (ref "Q21") (pin "3") (pinfunction "C_3") (pintype "passive"))
      (node (ref "R37") (pin "1") (pinfunction "1_1") (pintype "passive"))
    )
    (net (code "100") (name "Net-(U1-VBAT)") (class "Default")
      (node (ref "C4") (pin "1") (pinfunction "1_1") (pintype "passive"))
      (node (ref "R13") (pin "2") (pinfunction "2_2") (pintype "passive"))
      (node (ref "U1") (pin "3") (pinfunction "VBAT_3") (pintype "power_in"))
    )
    (net (code "101") (name "Net-(U1-X1)") (class "Default")
      (node (ref "C2") (pin "1") (pinfunction "1_1") (pintype "passive"))
      (node (ref "U1") (pin "1") (pinfunction "X1_1") (pintype "passive"))
      (node (ref "X1") (pin "1") (pinfunction "OSC1_1") (pintype "passive"))
    )
    (net (code "102") (name "Net-(U1-X2)") (class "Default")
      (node (ref "C3") (pin "1") (pinfunction "1_1") (pintype "passive"))
      (node (ref "U1") (pin "2") (pinfunction "X2_2") (pintype "passive"))
      (node (ref "X1") (pin "2") (pinfunction "OSC2_2") (pintype "passive"))
    )
    (net (code "103") (name "Net-(U2-A)") (class "Default")
      (node (ref "CN10") (pin "1") (pinfunction "1_1") (pintype "passive"))
      (node (ref "R50") (pin "2") (pinfunction "2_2") (pintype "passive"))
      (node (ref "U2") (pin "8") (pinfunction "A_8") (pintype "input"))
    )
    (net (code "104") (name "Net-(U2-B)") (class "Default")
      (node (ref "CN10") (pin "2") (pinfunction "2_2") (pintype "passive"))
      (node (ref "R50") (pin "1") (pinfunction "1_1") (pintype "passive"))
      (node (ref "U2") (pin "7") (pinfunction "B_7") (pintype "input"))
    )
    (net (code "105") (name "Net-(U2-Y)") (class "Default")
      (node (ref "CN8") (pin "1") (pinfunction "1_1") (pintype "passive"))
      (node (ref "R49") (pin "1") (pinfunction "1_1") (pintype "passive"))
      (node (ref "U2") (pin "5") (pinfunction "Y_5") (pintype "output"))
    )
    (net (code "106") (name "Net-(U2-Z)") (class "Default")
      (node (ref "CN8") (pin "2") (pinfunction "2_2") (pintype "passive"))
      (node (ref "R49") (pin "2") (pinfunction "2_2") (pintype "passive"))
      (node (ref "U2") (pin "6") (pinfunction "Z_6") (pintype "output"))
    )
    (net (code "107") (name "unconnected-(CN7-Pad28)") (class "Default")
      (node (ref "CN7") (pin "28") (pinfunction "28_28") (pintype "passive"))
    )
    (net (code "108") (name "unconnected-(CN7-Pad31)") (class "Default")
      (node (ref "CN7") (pin "31") (pinfunction "31_31") (pintype "passive"))
    )
    (net (code "109") (name "unconnected-(CN7-Pad32)") (class "Default")
      (node (ref "CN7") (pin "32") (pinfunction "32_32") (pintype "passive"))
    )
    (net (code "110") (name "unconnected-(CN7-Pad33)") (class "Default")
      (node (ref "CN7") (pin "33") (pinfunction "33_33") (pintype "passive"))
    )
    (net (code "111") (name "unconnected-(CN7-Pad35)") (class "Default")
      (node (ref "CN7") (pin "35") (pinfunction "35_35") (pintype "passive"))
    )
    (net (code "112") (name "unconnected-(CN7-Pad37)") (class "Default")
      (node (ref "CN7") (pin "37") (pinfunction "37_37") (pintype "passive"))
    )
    (net (code "113") (name "unconnected-(CN7-Pad39)") (class "Default")
      (node (ref "CN7") (pin "39") (pinfunction "39_39") (pintype "passive"))
    )
  )
)
